# schematic.net
KiCad netlist of a schematic drawn in EAGLE
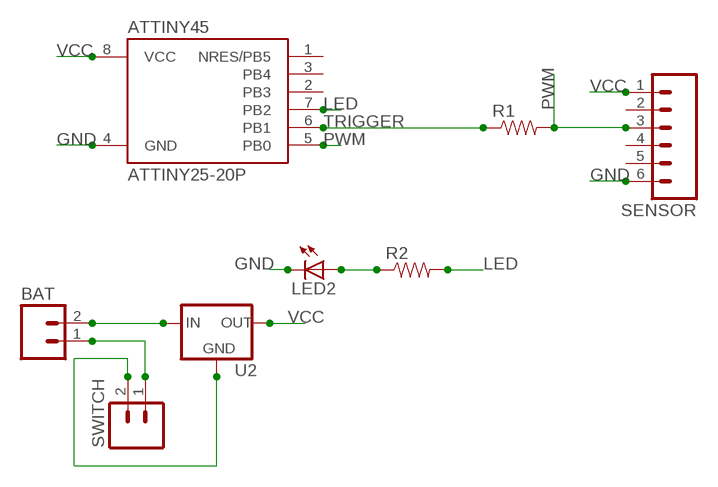
[diagram p0: schematic, sheet 1]

(export (version "E")
  (design (tool "Eeschema 10.0.6"))
  (components
    (comp (ref "ATTINY45")
      (value "ATTINY25-20P")
      (footprint "eagle-import:PDIP08_300MIL")
      (libsource (lib "eagle-import") (part "ATTINY25P-20"))
    )
    (comp (ref "BAT")
      (value "M02PTH")
      (footprint "eagle-import:1X02")
      (libsource (lib "eagle-import") (part "M02PTH"))
    )
    (comp (ref "LED2")
      (value "LED3MM")
      (footprint "eagle-import:LED3MM")
      (libsource (lib "eagle-import") (part "LED3MM"))
    )
    (comp (ref "R1")
      (value "10KOHM-1/6W-5%(PTH)KIT")
      (footprint "eagle-import:AXIAL-0.3-KIT")
      (libsource (lib "eagle-import") (part "10KOHM-1/6W-5%(PTH)KIT"))
    )
    (comp (ref "R2")
      (value "10KOHM-1/6W-5%(PTH)KIT")
      (footprint "eagle-import:AXIAL-0.3-KIT")
      (libsource (lib "eagle-import") (part "10KOHM-1/6W-5%(PTH)KIT"))
    )
    (comp (ref "SENSOR")
      (value "M06NO_SILK_FEMALE_PTH")
      (footprint "eagle-import:1X06_NO_SILK")
      (libsource (lib "eagle-import") (part "M06NO_SILK_FEMALE_PTH"))
    )
    (comp (ref "SWITCH")
      (value "M02PTH")
      (footprint "eagle-import:1X02")
      (libsource (lib "eagle-import") (part "M02PTH"))
    )
    (comp (ref "U2")
      (value "V_REG_78XX-TO-220")
      (footprint "eagle-import:TO-220-ALT")
      (libsource (lib "eagle-import") (part "V_REG_78XX-TO-220"))
    )
  )
  (nets
    (net (code "1") (name "/GND") (class "Default")
      (node (ref "ATTINY45") (pin "4") (pinfunction "GND_4") (pintype "power_in"))
      (node (ref "LED2") (pin "K") (pinfunction "C_K") (pintype "passive"))
      (node (ref "SENSOR") (pin "6") (pinfunction "6_6") (pintype "passive"))
      (node (ref "SWITCH") (pin "2") (pinfunction "2_2") (pintype "passive"))
      (node (ref "U2") (pin "GND") (pinfunction "GND_GND") (pintype "input"))
    )
    (net (code "2") (name "/LED") (class "Default")
      (node (ref "ATTINY45") (pin "7") (pinfunction "PB2_7") (pintype "bidirectional"))
      (node (ref "R2") (pin "P$2") (pinfunction "2_P$2") (pintype "passive"))
    )
    (net (code "3") (name "/PWM") (class "Default")
      (node (ref "ATTINY45") (pin "5") (pinfunction "PB0_5") (pintype "bidirectional"))
      (node (ref "R1") (pin "P$2") (pinfunction "2_P$2") (pintype "passive"))
      (node (ref "SENSOR") (pin "3") (pinfunction "3_3") (pintype "passive"))
    )
    (net (code "4") (name "/TRIGGER") (class "Default")
      (node (ref "ATTINY45") (pin "6") (pinfunction "PB1_6") (pintype "bidirectional"))
      (node (ref "R1") (pin "P$1") (pinfunction "1_P$1") (pintype "passive"))
    )
    (net (code "5") (name "/VCC") (class "Default")
      (node (ref "ATTINY45") (pin "8") (pinfunction "VCC_8") (pintype "power_in"))
      (node (ref "SENSOR") (pin "1") (pinfunction "1_1") (pintype "passive"))
      (node (ref "U2") (pin "OUT") (pinfunction "OUT_OUT") (pintype "passive"))
    )
    (net (code "6") (name "Net-(BAT-Pad1)") (class "Default")
      (node (ref "BAT") (pin "1") (pinfunction "1_1") (pintype "passive"))
      (node (ref "SWITCH") (pin "1") (pinfunction "1_1") (pintype "passive"))
    )
    (net (code "7") (name "Net-(BAT-Pad2)") (class "Default")
      (node (ref "BAT") (pin "2") (pinfunction "2_2") (pintype "passive"))
      (node (ref "U2") (pin "IN") (pinfunction "IN_IN") (pintype "input"))
    )
    (net (code "8") (name "Net-(R2-1)") (class "Default")
      (node (ref "LED2") (pin "A") (pinfunction "A_A") (pintype "passive"))
      (node (ref "R2") (pin "P$1") (pinfunction "1_P$1") (pintype "passive"))
    )
    (net (code "9") (name "unconnected-(ATTINY45-NRES{slash}PB5-Pad1)") (class "Default")
      (node (ref "ATTINY45") (pin "1") (pinfunction "NRES/PB5_1") (pintype "bidirectional"))
    )
    (net (code "10") (name "unconnected-(ATTINY45-PB3-Pad2)") (class "Default")
      (node (ref "ATTINY45") (pin "2") (pinfunction "PB3_2") (pintype "bidirectional"))
    )
    (net (code "11") (name "unconnected-(ATTINY45-PB4-Pad3)") (class "Default")
      (node (ref "ATTINY45") (pin "3") (pinfunction "PB4_3") (pintype "bidirectional"))
    )
    (net (code "12") (name "unconnected-(SENSOR-Pad2)") (class "Default")
      (node (ref "SENSOR") (pin "2") (pinfunction "2_2") (pintype "passive"))
    )
    (net (code "13") (name "unconnected-(SENSOR-Pad4)") (class "Default")
      (node (ref "SENSOR") (pin "4") (pinfunction "4_4") (pintype "passive"))
    )
    (net (code "14") (name "unconnected-(SENSOR-Pad5)") (class "Default")
      (node (ref "SENSOR") (pin "5") (pinfunction "5_5") (pintype "passive"))
    )
  )
)
